# FCC3_Micro.net
KiCad netlist of a schematic drawn in EAGLE
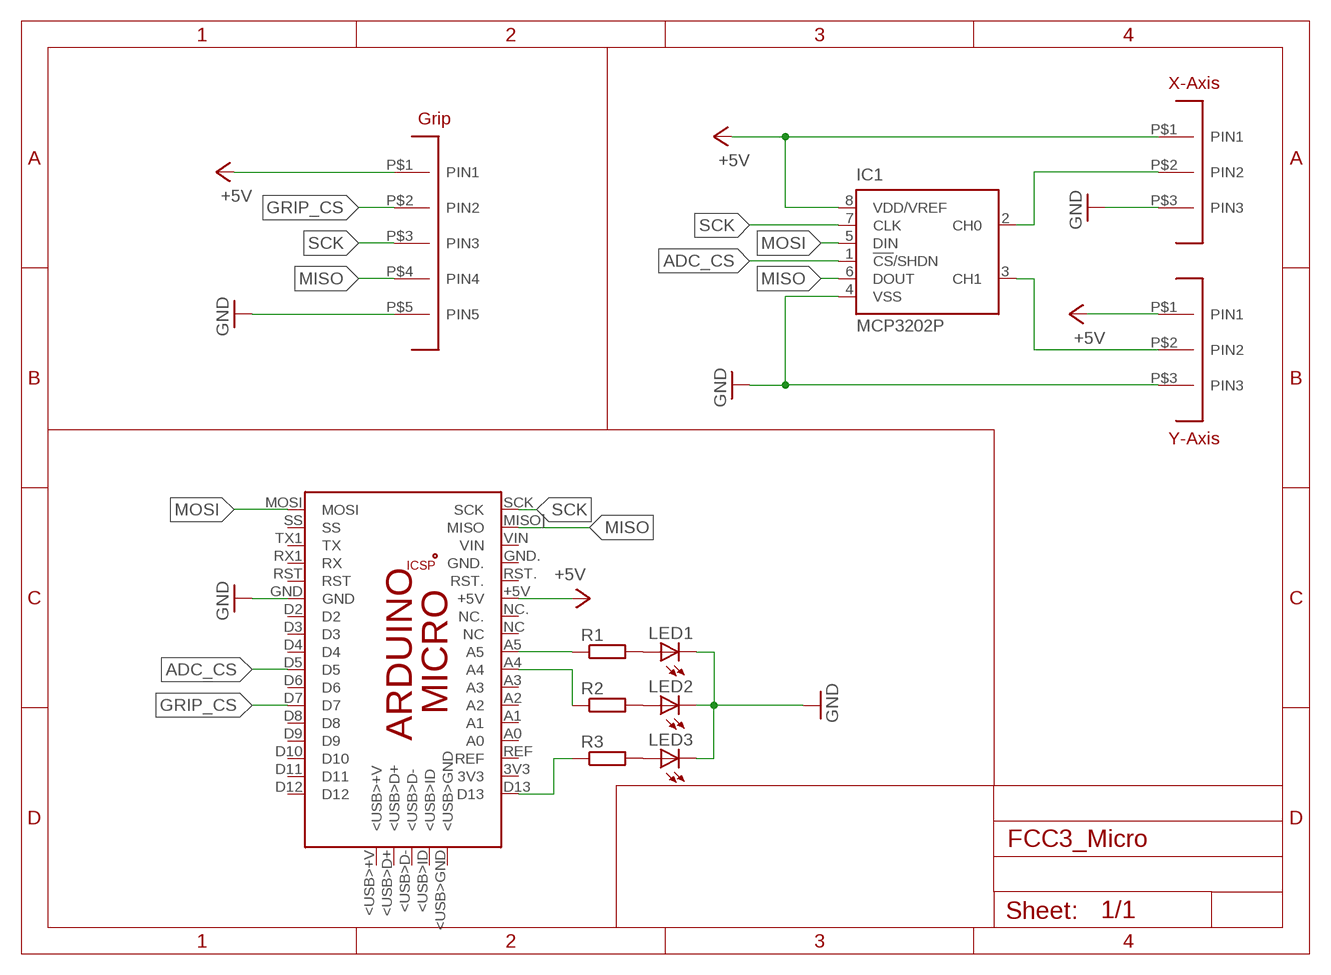
[diagram p0: schematic, sheet 1]

(export (version "E")
  (design (tool "Eeschema 10.0.6"))
  (components
    (comp (ref "IC1")
      (value "MCP3202P")
      (footprint "eagle-import:DIL8")
      (fields (field (name "MF") "MICROCHIP") (field (name "MPN") "MCP3202-CI/P"))
      (libsource (lib "eagle-import") (part "MCP3202P"))
    )
    (comp (ref "LED1")
      (value "LED5MM")
      (footprint "eagle-import:LED5MM")
      (libsource (lib "eagle-import") (part "LED5MM"))
    )
    (comp (ref "LED2")
      (value "LED5MM")
      (footprint "eagle-import:LED5MM")
      (libsource (lib "eagle-import") (part "LED5MM"))
    )
    (comp (ref "LED3")
      (value "LED5MM")
      (footprint "eagle-import:LED5MM")
      (libsource (lib "eagle-import") (part "LED5MM"))
    )
    (comp (ref "PCB1")
      (value "ARDUINO_MICRO")
      (footprint "eagle-import:ARDUINO_MICRO")
      (libsource (lib "eagle-import") (part "ARDUINO_MICRO"))
    )
    (comp (ref "R1")
      (value "R-EU_0204/5")
      (footprint "eagle-import:0204_5")
      (libsource (lib "eagle-import") (part "R-EU_0204/5"))
    )
    (comp (ref "R2")
      (value "R-EU_0204/5")
      (footprint "eagle-import:0204_5")
      (libsource (lib "eagle-import") (part "R-EU_0204/5"))
    )
    (comp (ref "R3")
      (value "R-EU_0204/5")
      (footprint "eagle-import:0204_5")
      (libsource (lib "eagle-import") (part "R-EU_0204/5"))
    )
    (comp (ref "U$1")
      (value "JST_EH_3PIN")
      (footprint "eagle-import:JST-EH-3PIN")
      (libsource (lib "eagle-import") (part "JST_EH_3PIN"))
    )
    (comp (ref "U$2")
      (value "JST_EH_3PIN")
      (footprint "eagle-import:JST-EH-3PIN")
      (libsource (lib "eagle-import") (part "JST_EH_3PIN"))
    )
    (comp (ref "U$3")
      (value "JST_EH_5PIN")
      (footprint "eagle-import:JST-EH-5PIN")
      (libsource (lib "eagle-import") (part "JST_EH_5PIN"))
    )
  )
  (nets
    (net (code "1") (name "+5V") (class "Default")
      (node (ref "IC1") (pin "8") (pinfunction "VDD/VREF_8") (pintype "input"))
      (node (ref "PCB1") (pin "+5V") (pinfunction "+5V_+5V") (pintype "bidirectional"))
      (node (ref "U$1") (pin "P$1") (pinfunction "PIN1_P$1") (pintype "bidirectional"))
      (node (ref "U$2") (pin "P$1") (pinfunction "PIN1_P$1") (pintype "bidirectional"))
      (node (ref "U$3") (pin "P$1") (pinfunction "PIN1_P$1") (pintype "bidirectional"))
    )
    (net (code "2") (name "ADC_CS") (class "Default")
      (node (ref "IC1") (pin "1") (pinfunction "~{CS}/SHDN_1") (pintype "input"))
      (node (ref "PCB1") (pin "D5") (pinfunction "D5_D5") (pintype "bidirectional"))
    )
    (net (code "3") (name "GND") (class "Default")
      (node (ref "IC1") (pin "4") (pinfunction "VSS_4") (pintype "input"))
      (node (ref "LED1") (pin "K") (pinfunction "C_K") (pintype "passive"))
      (node (ref "LED2") (pin "K") (pinfunction "C_K") (pintype "passive"))
      (node (ref "LED3") (pin "K") (pinfunction "C_K") (pintype "passive"))
      (node (ref "PCB1") (pin "GND") (pinfunction "GND_GND") (pintype "bidirectional"))
      (node (ref "U$1") (pin "P$3") (pinfunction "PIN3_P$3") (pintype "bidirectional"))
      (node (ref "U$2") (pin "P$3") (pinfunction "PIN3_P$3") (pintype "bidirectional"))
      (node (ref "U$3") (pin "P$5") (pinfunction "PIN5_P$5") (pintype "bidirectional"))
    )
    (net (code "4") (name "GRIP_CS") (class "Default")
      (node (ref "PCB1") (pin "D7") (pinfunction "D7_D7") (pintype "bidirectional"))
      (node (ref "U$3") (pin "P$2") (pinfunction "PIN2_P$2") (pintype "bidirectional"))
    )
    (net (code "5") (name "MISO") (class "Default")
      (node (ref "IC1") (pin "6") (pinfunction "DOUT_6") (pintype "input"))
      (node (ref "PCB1") (pin "MISO]") (pinfunction "MISO_MISO]") (pintype "bidirectional"))
      (node (ref "U$3") (pin "P$4") (pinfunction "PIN4_P$4") (pintype "bidirectional"))
    )
    (net (code "6") (name "MOSI") (class "Default")
      (node (ref "IC1") (pin "5") (pinfunction "DIN_5") (pintype "input"))
      (node (ref "PCB1") (pin "MOSI") (pinfunction "MOSI_MOSI") (pintype "bidirectional"))
    )
    (net (code "7") (name "Net-(IC1-CH0)") (class "Default")
      (node (ref "IC1") (pin "2") (pinfunction "CH0_2") (pintype "input"))
      (node (ref "U$2") (pin "P$2") (pinfunction "PIN2_P$2") (pintype "bidirectional"))
    )
    (net (code "8") (name "Net-(IC1-CH1)") (class "Default")
      (node (ref "IC1") (pin "3") (pinfunction "CH1_3") (pintype "input"))
      (node (ref "U$1") (pin "P$2") (pinfunction "PIN2_P$2") (pintype "bidirectional"))
    )
    (net (code "9") (name "Net-(LED1-PadA)") (class "Default")
      (node (ref "LED1") (pin "A") (pinfunction "A_A") (pintype "passive"))
      (node (ref "R1") (pin "2") (pinfunction "2_2") (pintype "passive"))
    )
    (net (code "10") (name "Net-(LED2-PadA)") (class "Default")
      (node (ref "LED2") (pin "A") (pinfunction "A_A") (pintype "passive"))
      (node (ref "R2") (pin "2") (pinfunction "2_2") (pintype "passive"))
    )
    (net (code "11") (name "Net-(LED3-PadA)") (class "Default")
      (node (ref "LED3") (pin "A") (pinfunction "A_A") (pintype "passive"))
      (node (ref "R3") (pin "2") (pinfunction "2_2") (pintype "passive"))
    )
    (net (code "12") (name "Net-(PCB1-PadA4)") (class "Default")
      (node (ref "PCB1") (pin "A4") (pinfunction "A4_A4") (pintype "bidirectional"))
      (node (ref "R2") (pin "1") (pinfunction "1_1") (pintype "passive"))
    )
    (net (code "13") (name "Net-(PCB1-PadA5)") (class "Default")
      (node (ref "PCB1") (pin "A5") (pinfunction "A5_A5") (pintype "bidirectional"))
      (node (ref "R1") (pin "1") (pinfunction "1_1") (pintype "passive"))
    )
    (net (code "14") (name "Net-(PCB1-PadD13)") (class "Default")
      (node (ref "PCB1") (pin "D13") (pinfunction "D13_D13") (pintype "bidirectional"))
      (node (ref "R3") (pin "1") (pinfunction "1_1") (pintype "passive"))
    )
    (net (code "15") (name "SCK") (class "Default")
      (node (ref "IC1") (pin "7") (pinfunction "CLK_7") (pintype "input"))
      (node (ref "PCB1") (pin "SCK") (pinfunction "SCK_SCK") (pintype "bidirectional"))
      (node (ref "U$3") (pin "P$3") (pinfunction "PIN3_P$3") (pintype "bidirectional"))
    )
    (net (code "16") (name "unconnected-(PCB1-Pad3V3)") (class "Default")
      (node (ref "PCB1") (pin "3V3") (pinfunction "3V3_3V3") (pintype "bidirectional"))
    )
    (net (code "17") (name "unconnected-(PCB1-Pad5V)") (class "Default")
      (node (ref "PCB1") (pin "5V") (pinfunction "5V_5V") (pintype "bidirectional"))
    )
    (net (code "18") (name "unconnected-(PCB1-Pad<USB>+V)") (class "Default")
      (node (ref "PCB1") (pin "<USB>+V") (pinfunction "<USB>+V_<USB>+V") (pintype "bidirectional"))
    )
    (net (code "19") (name "unconnected-(PCB1-Pad<USB>D+)") (class "Default")
      (node (ref "PCB1") (pin "<USB>D+") (pinfunction "<USB>D+_<USB>D+") (pintype "bidirectional"))
    )
    (net (code "20") (name "unconnected-(PCB1-Pad<USB>D-)") (class "Default")
      (node (ref "PCB1") (pin "<USB>D-") (pinfunction "<USB>D-_<USB>D-") (pintype "bidirectional"))
    )
    (net (code "21") (name "unconnected-(PCB1-Pad<USB>GND)") (class "Default")
      (node (ref "PCB1") (pin "<USB>GND") (pinfunction "<USB>GND_<USB>GND") (pintype "bidirectional"))
    )
    (net (code "22") (name "unconnected-(PCB1-Pad<USB>ID)") (class "Default")
      (node (ref "PCB1") (pin "<USB>ID") (pinfunction "<USB>ID_<USB>ID") (pintype "bidirectional"))
    )
    (net (code "23") (name "unconnected-(PCB1-PadA0)") (class "Default")
      (node (ref "PCB1") (pin "A0") (pinfunction "A0_A0") (pintype "bidirectional"))
    )
    (net (code "24") (name "unconnected-(PCB1-PadA1)") (class "Default")
      (node (ref "PCB1") (pin "A1") (pinfunction "A1_A1") (pintype "bidirectional"))
    )
    (net (code "25") (name "unconnected-(PCB1-PadA2)") (class "Default")
      (node (ref "PCB1") (pin "A2") (pinfunction "A2_A2") (pintype "bidirectional"))
    )
    (net (code "26") (name "unconnected-(PCB1-PadA3)") (class "Default")
      (node (ref "PCB1") (pin "A3") (pinfunction "A3_A3") (pintype "bidirectional"))
    )
    (net (code "27") (name "unconnected-(PCB1-PadD2)") (class "Default")
      (node (ref "PCB1") (pin "D2") (pinfunction "D2_D2") (pintype "bidirectional"))
    )
    (net (code "28") (name "unconnected-(PCB1-PadD3)") (class "Default")
      (node (ref "PCB1") (pin "D3") (pinfunction "D3_D3") (pintype "bidirectional"))
    )
    (net (code "29") (name "unconnected-(PCB1-PadD4)") (class "Default")
      (node (ref "PCB1") (pin "D4") (pinfunction "D4_D4") (pintype "bidirectional"))
    )
    (net (code "30") (name "unconnected-(PCB1-PadD6)") (class "Default")
      (node (ref "PCB1") (pin "D6") (pinfunction "D6_D6") (pintype "bidirectional"))
    )
    (net (code "31") (name "unconnected-(PCB1-PadD8)") (class "Default")
      (node (ref "PCB1") (pin "D8") (pinfunction "D8_D8") (pintype "bidirectional"))
    )
    (net (code "32") (name "unconnected-(PCB1-PadD9)") (class "Default")
      (node (ref "PCB1") (pin "D9") (pinfunction "D9_D9") (pintype "bidirectional"))
    )
    (net (code "33") (name "unconnected-(PCB1-PadD10)") (class "Default")
      (node (ref "PCB1") (pin "D10") (pinfunction "D10_D10") (pintype "bidirectional"))
    )
    (net (code "34") (name "unconnected-(PCB1-PadD11)") (class "Default")
      (node (ref "PCB1") (pin "D11") (pinfunction "D11_D11") (pintype "bidirectional"))
    )
    (net (code "35") (name "unconnected-(PCB1-PadD12)") (class "Default")
      (node (ref "PCB1") (pin "D12") (pinfunction "D12_D12") (pintype "bidirectional"))
    )
    (net (code "36") (name "unconnected-(PCB1-PadGND.)") (class "Default")
      (node (ref "PCB1") (pin "GND.") (pinfunction "GND._GND.") (pintype "bidirectional"))
    )
    (net (code "37") (name "unconnected-(PCB1-PadGND_)") (class "Default")
      (node (ref "PCB1") (pin "GND_") (pinfunction "GND__GND_") (pintype "bidirectional"))
    )
    (net (code "38") (name "unconnected-(PCB1-PadMISO.)") (class "Default")
      (node (ref "PCB1") (pin "MISO.") (pinfunction "MISO._MISO.") (pintype "bidirectional"))
    )
    (net (code "39") (name "unconnected-(PCB1-PadMOSI.)") (class "Default")
      (node (ref "PCB1") (pin "MOSI.") (pinfunction "MOSI._MOSI.") (pintype "bidirectional"))
    )
    (net (code "40") (name "unconnected-(PCB1-PadNC)") (class "Default")
      (node (ref "PCB1") (pin "NC") (pinfunction "NC_NC") (pintype "bidirectional"))
    )
    (net (code "41") (name "unconnected-(PCB1-PadNC.)") (class "Default")
      (node (ref "PCB1") (pin "NC.") (pinfunction "NC._NC.") (pintype "bidirectional"))
    )
    (net (code "42") (name "unconnected-(PCB1-PadREF)") (class "Default")
      (node (ref "PCB1") (pin "REF") (pinfunction "REF_REF") (pintype "bidirectional"))
    )
    (net (code "43") (name "unconnected-(PCB1-PadRESET..)") (class "Default")
      (node (ref "PCB1") (pin "RESET..") (pinfunction "RESET.._RESET..") (pintype "bidirectional"))
    )
    (net (code "44") (name "unconnected-(PCB1-PadRST)") (class "Default")
      (node (ref "PCB1") (pin "RST") (pinfunction "RST_RST") (pintype "bidirectional"))
    )
    (net (code "45") (name "unconnected-(PCB1-PadRST.)") (class "Default")
      (node (ref "PCB1") (pin "RST.") (pinfunction "RST._RST.") (pintype "bidirectional"))
    )
    (net (code "46") (name "unconnected-(PCB1-PadSCK.)") (class "Default")
      (node (ref "PCB1") (pin "SCK.") (pinfunction "SCK._SCK.") (pintype "bidirectional"))
    )
    (net (code "47") (name "unconnected-(PCB1-PadSS)") (class "Default")
      (node (ref "PCB1") (pin "SS") (pinfunction "SS_SS") (pintype "bidirectional"))
    )
    (net (code "48") (name "unconnected-(PCB1-PadVIN)") (class "Default")
      (node (ref "PCB1") (pin "VIN") (pinfunction "VIN_VIN") (pintype "bidirectional"))
    )
    (net (code "49") (name "unconnected-(PCB1-RX-PadRX1)") (class "Default")
      (node (ref "PCB1") (pin "RX1") (pinfunction "RX_RX1") (pintype "bidirectional"))
    )
    (net (code "50") (name "unconnected-(PCB1-TX-PadTX1)") (class "Default")
      (node (ref "PCB1") (pin "TX1") (pinfunction "TX_TX1") (pintype "bidirectional"))
    )
  )
)
